# BMS_Temp.net
KiCad netlist of a schematic drawn in Altium Designer
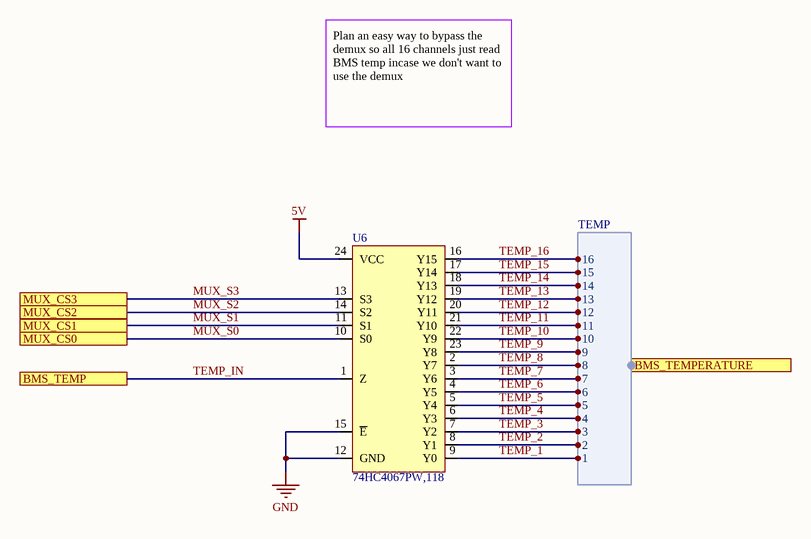
[diagram p0: BMS_Temp.SchDoc]

(export (version "E")
  (design (tool "Eeschema 10.0.6"))
  (components
    (comp (ref "U6")
      (value "74HC4067PW,118")
      (footprint "24-TSSOP")
      (description "IC MUX/DEMUX 1X16 24TSSOP")
      (fields (field (name "MANUFACTURER") "Nexperia USA"))
      (libsource (lib "ICs") (part "MUX-74HC4067"))
    )
  )
  (nets
    (net (code "2") (name "/MUX_S0") (class "Default")
      (node (ref "U6") (pin "10") (pinfunction "S0_10") (pintype "passive"))
    )
    (net (code "3") (name "/MUX_S1") (class "Default")
      (node (ref "U6") (pin "11") (pinfunction "S1_11") (pintype "passive"))
    )
    (net (code "4") (name "/MUX_S2") (class "Default")
      (node (ref "U6") (pin "14") (pinfunction "S2_14") (pintype "passive"))
    )
    (net (code "5") (name "/MUX_S3") (class "Default")
      (node (ref "U6") (pin "13") (pinfunction "S3_13") (pintype "passive"))
    )
    (net (code "6") (name "/TEMP_1") (class "Default")
      (node (ref "U6") (pin "9") (pinfunction "Y0_9") (pintype "passive"))
    )
    (net (code "7") (name "/TEMP_2") (class "Default")
      (node (ref "U6") (pin "8") (pinfunction "Y1_8") (pintype "passive"))
    )
    (net (code "8") (name "/TEMP_3") (class "Default")
      (node (ref "U6") (pin "7") (pinfunction "Y2_7") (pintype "passive"))
    )
    (net (code "9") (name "/TEMP_4") (class "Default")
      (node (ref "U6") (pin "6") (pinfunction "Y3_6") (pintype "passive"))
    )
    (net (code "10") (name "/TEMP_5") (class "Default")
      (node (ref "U6") (pin "5") (pinfunction "Y4_5") (pintype "passive"))
    )
    (net (code "11") (name "/TEMP_6") (class "Default")
      (node (ref "U6") (pin "4") (pinfunction "Y5_4") (pintype "passive"))
    )
    (net (code "12") (name "/TEMP_7") (class "Default")
      (node (ref "U6") (pin "3") (pinfunction "Y6_3") (pintype "passive"))
    )
    (net (code "13") (name "/TEMP_8") (class "Default")
      (node (ref "U6") (pin "2") (pinfunction "Y7_2") (pintype "passive"))
    )
    (net (code "14") (name "/TEMP_9") (class "Default")
      (node (ref "U6") (pin "23") (pinfunction "Y8_23") (pintype "passive"))
    )
    (net (code "15") (name "/TEMP_10") (class "Default")
      (node (ref "U6") (pin "22") (pinfunction "Y9_22") (pintype "passive"))
    )
    (net (code "16") (name "/TEMP_11") (class "Default")
      (node (ref "U6") (pin "21") (pinfunction "Y10_21") (pintype "passive"))
    )
    (net (code "17") (name "/TEMP_12") (class "Default")
      (node (ref "U6") (pin "20") (pinfunction "Y11_20") (pintype "passive"))
    )
    (net (code "18") (name "/TEMP_13") (class "Default")
      (node (ref "U6") (pin "19") (pinfunction "Y12_19") (pintype "passive"))
    )
    (net (code "19") (name "/TEMP_14") (class "Default")
      (node (ref "U6") (pin "18") (pinfunction "Y13_18") (pintype "passive"))
    )
    (net (code "20") (name "/TEMP_15") (class "Default")
      (node (ref "U6") (pin "17") (pinfunction "Y14_17") (pintype "passive"))
    )
    (net (code "21") (name "/TEMP_16") (class "Default")
      (node (ref "U6") (pin "16") (pinfunction "Y15_16") (pintype "passive"))
    )
    (net (code "22") (name "/TEMP_IN") (class "Default")
      (node (ref "U6") (pin "1") (pinfunction "Z_1") (pintype "passive"))
    )
    (net (code "24") (name "5V") (class "Default")
      (node (ref "U6") (pin "24") (pinfunction "VCC_24") (pintype "passive"))
    )
    (net (code "25") (name "GND") (class "Default")
      (node (ref "U6") (pin "12") (pinfunction "GND_12") (pintype "passive"))
      (node (ref "U6") (pin "15") (pinfunction "~{E}_15") (pintype "passive"))
    )
  )
)
